# motherboard.net
KiCad netlist of a schematic drawn in Altium Designer
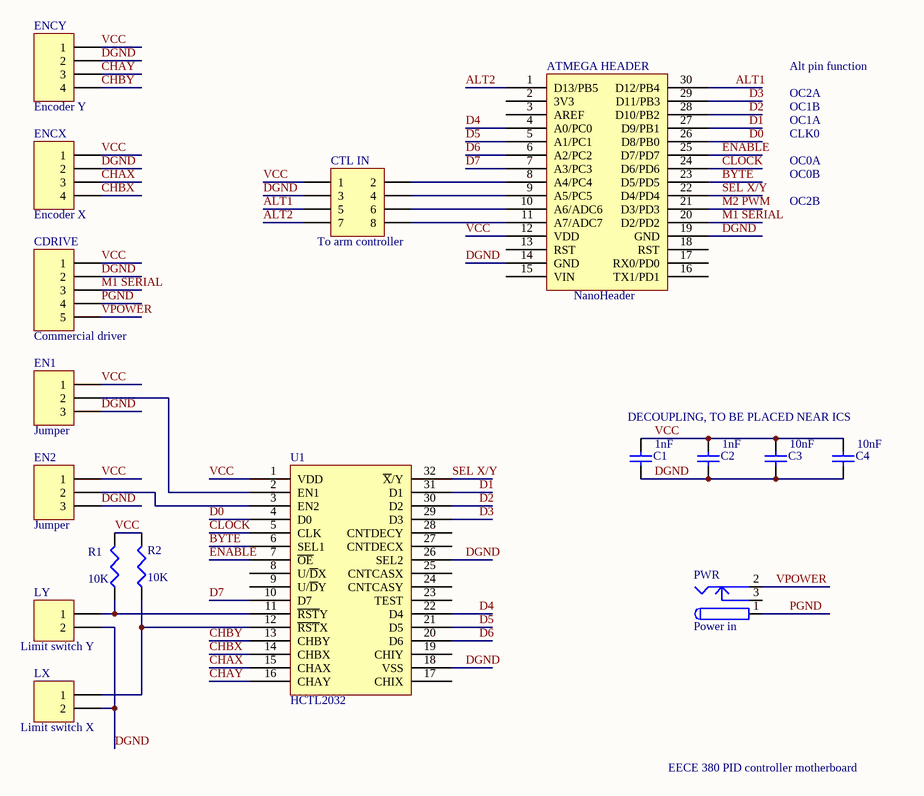
[diagram p0: motherboard.SchDoc]

(export (version "E")
  (design (tool "Eeschema 10.0.6"))
  (components
    (comp (ref "ATMEGA HEADER")
      (value "NanoHeader")
      (footprint "DIP30WIDE")
      (libsource (lib "controllerSchLib") (part "NanoHeader"))
    )
    (comp (ref "C1")
      (value "1nF")
      (footprint "RAD-0.3")
      (description "Capacitor")
      (fields (field (name "PUBLISHER") "Altium Limited"))
      (libsource (lib "Miscellaneous Devices") (part "Cap"))
    )
    (comp (ref "C2")
      (value "1nF")
      (footprint "RAD-0.3")
      (description "Capacitor")
      (fields (field (name "PUBLISHER") "Altium Limited"))
      (libsource (lib "Miscellaneous Devices") (part "Cap"))
    )
    (comp (ref "C3")
      (value "10nF")
      (footprint "RAD-0.3")
      (description "Capacitor")
      (fields (field (name "PUBLISHER") "Altium Limited"))
      (libsource (lib "Miscellaneous Devices") (part "Cap"))
    )
    (comp (ref "C4")
      (value "10nF")
      (footprint "RAD-0.3")
      (description "Capacitor")
      (fields (field (name "PUBLISHER") "Altium Limited"))
      (libsource (lib "Miscellaneous Devices") (part "Cap"))
    )
    (comp (ref "CDRIVE")
      (value "Commercial driver")
      (footprint "HDR1X5_LGE1.0")
      (description "Header, 6-Pin")
      (fields (field (name "PUBLISHER") "Altium Limited"))
      (libsource (lib "PartsDatabaseV13p1") (part "C-Hdr1x5"))
    )
    (comp (ref "CTL IN")
      (value "To arm controller")
      (footprint "HDR2X4_LGE1.0")
      (description "Header, 4-Pin, Dual row")
      (fields (field (name "PUBLISHER") "Altium Limited"))
      (libsource (lib "PartsDatabaseV13p1") (part "C-Hdr2x4"))
    )
    (comp (ref "EN1")
      (value "Jumper")
      (footprint "HDR1X3_LGE1.0")
      (description "Header, 4-Pin")
      (fields (field (name "PUBLISHER") "Altium Limited"))
      (libsource (lib "PartsDatabaseV13p1") (part "C-Hdr1x3"))
    )
    (comp (ref "EN2")
      (value "Jumper")
      (footprint "HDR1X3_LGE1.0")
      (description "Header, 4-Pin")
      (fields (field (name "PUBLISHER") "Altium Limited"))
      (libsource (lib "PartsDatabaseV13p1") (part "C-Hdr1x3"))
    )
    (comp (ref "ENCX")
      (value "Encoder X")
      (footprint "HDR1X4_LGE1.0")
      (description "Header, 4-Pin")
      (fields (field (name "PUBLISHER") "Altium Limited"))
      (libsource (lib "PartsDatabaseV12") (part "C-Hdr1x4"))
    )
    (comp (ref "ENCY")
      (value "Encoder Y")
      (footprint "HDR1X4_LGE1.0")
      (description "Header, 4-Pin")
      (fields (field (name "PUBLISHER") "Altium Limited"))
      (libsource (lib "PartsDatabaseV12") (part "C-Hdr1x4"))
    )
    (comp (ref "LX")
      (value "Limit switch X")
      (footprint "HDR1X2_LGE1.0")
      (description "Header, 2-Pin")
      (fields (field (name "PUBLISHER") "Altium Limited"))
      (libsource (lib "PartsDatabaseV13p1") (part "C-Hdr1x2"))
    )
    (comp (ref "LY")
      (value "Limit switch Y")
      (footprint "HDR1X2_LGE1.0")
      (description "Header, 2-Pin")
      (fields (field (name "PUBLISHER") "Altium Limited"))
      (libsource (lib "PartsDatabaseV13p1") (part "C-Hdr1x2"))
    )
    (comp (ref "PWR")
      (value "Power in")
      (footprint "KLD_XLGE1.2")
      (description "Low Voltage Power Supply Connector")
      (fields (field (name "PUBLISHER") "Altium Limited"))
      (libsource (lib "PartsDatabaseV13p1") (part "C-Pwr"))
    )
    (comp (ref "R1")
      (value "10K")
      (footprint "Res10mm_LGE1.0")
      (description "resistor (specify value)")
      (fields (field (name "PUBLISHER") "Altium Limited"))
      (libsource (lib "PartsDatabaseV13p1") (part "G-Res"))
    )
    (comp (ref "R2")
      (value "10K")
      (footprint "Res10mm_LGE1.0")
      (description "resistor (specify value)")
      (fields (field (name "PUBLISHER") "Altium Limited"))
      (libsource (lib "PartsDatabaseV13p1") (part "G-Res"))
    )
    (comp (ref "U1")
      (value "HCTL2032")
      (footprint "SOIC50P295X100-32L16N")
      (libsource (lib "controllerSchLib") (part "HCTL2032"))
    )
  )
  (nets
    (net (code "1") (name "/ALT1") (class "Default")
      (node (ref "ATMEGA HEADER") (pin "30") (pinfunction "D12/PB4_30") (pintype "passive"))
      (node (ref "CTL IN") (pin "5") (pinfunction "5_5") (pintype "passive"))
    )
    (net (code "2") (name "/ALT2") (class "Default")
      (node (ref "ATMEGA HEADER") (pin "1") (pinfunction "D13/PB5_1") (pintype "passive"))
      (node (ref "CTL IN") (pin "7") (pinfunction "7_7") (pintype "passive"))
    )
    (net (code "3") (name "/BYTE") (class "Default")
      (node (ref "ATMEGA HEADER") (pin "23") (pinfunction "D5/PD5_23") (pintype "passive"))
      (node (ref "U1") (pin "6") (pinfunction "SEL1_6") (pintype "passive"))
    )
    (net (code "4") (name "/CHAX") (class "Default")
      (node (ref "ENCX") (pin "3") (pinfunction "3_3") (pintype "passive"))
      (node (ref "U1") (pin "15") (pinfunction "CHAX_15") (pintype "passive"))
    )
    (net (code "5") (name "/CHAY") (class "Default")
      (node (ref "ENCY") (pin "3") (pinfunction "3_3") (pintype "passive"))
      (node (ref "U1") (pin "16") (pinfunction "CHAY_16") (pintype "passive"))
    )
    (net (code "6") (name "/CHBX") (class "Default")
      (node (ref "ENCX") (pin "4") (pinfunction "4_4") (pintype "passive"))
      (node (ref "U1") (pin "14") (pinfunction "CHBX_14") (pintype "passive"))
    )
    (net (code "7") (name "/CHBY") (class "Default")
      (node (ref "ENCY") (pin "4") (pinfunction "4_4") (pintype "passive"))
      (node (ref "U1") (pin "13") (pinfunction "CHBY_13") (pintype "passive"))
    )
    (net (code "8") (name "/CLOCK") (class "Default")
      (node (ref "ATMEGA HEADER") (pin "24") (pinfunction "D6/PD6_24") (pintype "passive"))
      (node (ref "U1") (pin "5") (pinfunction "CLK_5") (pintype "passive"))
    )
    (net (code "9") (name "/D0") (class "Default")
      (node (ref "ATMEGA HEADER") (pin "26") (pinfunction "D8/PB0_26") (pintype "passive"))
      (node (ref "U1") (pin "4") (pinfunction "D0_4") (pintype "passive"))
    )
    (net (code "10") (name "/D1") (class "Default")
      (node (ref "ATMEGA HEADER") (pin "27") (pinfunction "D9/PB1_27") (pintype "passive"))
      (node (ref "U1") (pin "31") (pinfunction "D1_31") (pintype "passive"))
    )
    (net (code "11") (name "/D2") (class "Default")
      (node (ref "ATMEGA HEADER") (pin "28") (pinfunction "D10/PB2_28") (pintype "passive"))
      (node (ref "U1") (pin "30") (pinfunction "D2_30") (pintype "passive"))
    )
    (net (code "12") (name "/D3") (class "Default")
      (node (ref "ATMEGA HEADER") (pin "29") (pinfunction "D11/PB3_29") (pintype "passive"))
      (node (ref "U1") (pin "29") (pinfunction "D3_29") (pintype "passive"))
    )
    (net (code "13") (name "/D4") (class "Default")
      (node (ref "ATMEGA HEADER") (pin "4") (pinfunction "A0/PC0_4") (pintype "passive"))
      (node (ref "U1") (pin "22") (pinfunction "D4_22") (pintype "passive"))
    )
    (net (code "14") (name "/D5") (class "Default")
      (node (ref "ATMEGA HEADER") (pin "5") (pinfunction "A1/PC1_5") (pintype "passive"))
      (node (ref "U1") (pin "21") (pinfunction "D5_21") (pintype "passive"))
    )
    (net (code "15") (name "/D6") (class "Default")
      (node (ref "ATMEGA HEADER") (pin "6") (pinfunction "A2/PC2_6") (pintype "passive"))
      (node (ref "U1") (pin "20") (pinfunction "D6_20") (pintype "passive"))
    )
    (net (code "16") (name "/D7") (class "Default")
      (node (ref "ATMEGA HEADER") (pin "7") (pinfunction "A3/PC3_7") (pintype "passive"))
      (node (ref "U1") (pin "10") (pinfunction "D7_10") (pintype "passive"))
    )
    (net (code "17") (name "/DGND") (class "Default")
      (node (ref "ATMEGA HEADER") (pin "14") (pinfunction "GND_14") (pintype "passive"))
      (node (ref "ATMEGA HEADER") (pin "19") (pinfunction "GND_19") (pintype "passive"))
      (node (ref "C1") (pin "1") (pinfunction "1_1") (pintype "passive"))
      (node (ref "C2") (pin "1") (pinfunction "1_1") (pintype "passive"))
      (node (ref "C3") (pin "1") (pinfunction "1_1") (pintype "passive"))
      (node (ref "C4") (pin "1") (pinfunction "1_1") (pintype "passive"))
      (node (ref "CDRIVE") (pin "2") (pinfunction "2_2") (pintype "passive"))
      (node (ref "CTL IN") (pin "3") (pinfunction "3_3") (pintype "passive"))
      (node (ref "EN1") (pin "3") (pinfunction "3_3") (pintype "passive"))
      (node (ref "EN2") (pin "3") (pinfunction "3_3") (pintype "passive"))
      (node (ref "ENCX") (pin "2") (pinfunction "2_2") (pintype "passive"))
      (node (ref "ENCY") (pin "2") (pinfunction "2_2") (pintype "passive"))
      (node (ref "LX") (pin "2") (pinfunction "2_2") (pintype "passive"))
      (node (ref "LY") (pin "2") (pinfunction "2_2") (pintype "passive"))
      (node (ref "U1") (pin "18") (pinfunction "VSS_18") (pintype "passive"))
      (node (ref "U1") (pin "26") (pinfunction "SEL2_26") (pintype "passive"))
    )
    (net (code "18") (name "/ENABLE") (class "Default")
      (node (ref "ATMEGA HEADER") (pin "25") (pinfunction "D7/PD7_25") (pintype "passive"))
      (node (ref "U1") (pin "7") (pinfunction "~{OE}_7") (pintype "passive"))
    )
    (net (code "19") (name "/M1 SERIAL") (class "Default")
      (node (ref "ATMEGA HEADER") (pin "20") (pinfunction "D2/PD2_20") (pintype "passive"))
      (node (ref "CDRIVE") (pin "3") (pinfunction "3_3") (pintype "passive"))
    )
    (net (code "20") (name "/M2 PWM") (class "Default")
      (node (ref "ATMEGA HEADER") (pin "21") (pinfunction "D3/PD3_21") (pintype "passive"))
    )
    (net (code "21") (name "/PGND") (class "Default")
      (node (ref "CDRIVE") (pin "4") (pinfunction "4_4") (pintype "passive"))
      (node (ref "PWR") (pin "1") (pinfunction "1_1") (pintype "power_in"))
    )
    (net (code "22") (name "/SEL X{slash}Y") (class "Default")
      (node (ref "ATMEGA HEADER") (pin "22") (pinfunction "D4/PD4_22") (pintype "passive"))
      (node (ref "U1") (pin "32") (pinfunction "~{X}/Y_32") (pintype "passive"))
    )
    (net (code "23") (name "/VCC") (class "Default")
      (node (ref "ATMEGA HEADER") (pin "12") (pinfunction "VDD_12") (pintype "passive"))
      (node (ref "C1") (pin "2") (pinfunction "2_2") (pintype "passive"))
      (node (ref "C2") (pin "2") (pinfunction "2_2") (pintype "passive"))
      (node (ref "C3") (pin "2") (pinfunction "2_2") (pintype "passive"))
      (node (ref "C4") (pin "2") (pinfunction "2_2") (pintype "passive"))
      (node (ref "CDRIVE") (pin "1") (pinfunction "1_1") (pintype "passive"))
      (node (ref "CTL IN") (pin "1") (pinfunction "1_1") (pintype "passive"))
      (node (ref "EN1") (pin "1") (pinfunction "1_1") (pintype "passive"))
      (node (ref "EN2") (pin "1") (pinfunction "1_1") (pintype "passive"))
      (node (ref "ENCX") (pin "1") (pinfunction "1_1") (pintype "passive"))
      (node (ref "ENCY") (pin "1") (pinfunction "1_1") (pintype "passive"))
      (node (ref "R1") (pin "2") (pinfunction "2_2") (pintype "passive"))
      (node (ref "R2") (pin "2") (pinfunction "2_2") (pintype "passive"))
      (node (ref "U1") (pin "1") (pinfunction "VDD_1") (pintype "passive"))
    )
    (net (code "24") (name "/VPOWER") (class "Default")
      (node (ref "CDRIVE") (pin "5") (pinfunction "5_5") (pintype "passive"))
      (node (ref "PWR") (pin "2") (pinfunction "2_2") (pintype "power_in"))
    )
    (net (code "25") (name "Net-(ATMEGA HEADER-A4{slash}PC4)") (class "Default")
      (node (ref "ATMEGA HEADER") (pin "8") (pinfunction "A4/PC4_8") (pintype "passive"))
      (node (ref "CTL IN") (pin "2") (pinfunction "2_2") (pintype "passive"))
    )
    (net (code "26") (name "Net-(ATMEGA HEADER-A5{slash}PC5)") (class "Default")
      (node (ref "ATMEGA HEADER") (pin "9") (pinfunction "A5/PC5_9") (pintype "passive"))
      (node (ref "CTL IN") (pin "4") (pinfunction "4_4") (pintype "passive"))
    )
    (net (code "27") (name "Net-(ATMEGA HEADER-A6{slash}ADC6)") (class "Default")
      (node (ref "ATMEGA HEADER") (pin "10") (pinfunction "A6/ADC6_10") (pintype "passive"))
      (node (ref "CTL IN") (pin "6") (pinfunction "6_6") (pintype "passive"))
    )
    (net (code "28") (name "Net-(ATMEGA HEADER-A7{slash}ADC7)") (class "Default")
      (node (ref "ATMEGA HEADER") (pin "11") (pinfunction "A7/ADC7_11") (pintype "passive"))
      (node (ref "CTL IN") (pin "8") (pinfunction "8_8") (pintype "passive"))
    )
    (net (code "29") (name "Net-(U1-EN1)") (class "Default")
      (node (ref "EN1") (pin "2") (pinfunction "2_2") (pintype "passive"))
      (node (ref "U1") (pin "2") (pinfunction "EN1_2") (pintype "passive"))
    )
    (net (code "30") (name "Net-(U1-EN2)") (class "Default")
      (node (ref "EN2") (pin "2") (pinfunction "2_2") (pintype "passive"))
      (node (ref "U1") (pin "3") (pinfunction "EN2_3") (pintype "passive"))
    )
    (net (code "31") (name "Net-(U1-~{RST}X)") (class "Default")
      (node (ref "LX") (pin "1") (pinfunction "1_1") (pintype "passive"))
      (node (ref "R2") (pin "1") (pinfunction "1_1") (pintype "passive"))
      (node (ref "U1") (pin "12") (pinfunction "~{RST}X_12") (pintype "passive"))
    )
    (net (code "32") (name "Net-(U1-~{RST}Y)") (class "Default")
      (node (ref "LY") (pin "1") (pinfunction "1_1") (pintype "passive"))
      (node (ref "R1") (pin "1") (pinfunction "1_1") (pintype "passive"))
      (node (ref "U1") (pin "11") (pinfunction "~{RST}Y_11") (pintype "passive"))
    )
    (net (code "33") (name "unconnected-(ATMEGA HEADER-3V3-Pad2)") (class "Default")
      (node (ref "ATMEGA HEADER") (pin "2") (pinfunction "3V3_2") (pintype "passive"))
    )
    (net (code "34") (name "unconnected-(ATMEGA HEADER-AREF-Pad3)") (class "Default")
      (node (ref "ATMEGA HEADER") (pin "3") (pinfunction "AREF_3") (pintype "passive"))
    )
    (net (code "35") (name "unconnected-(ATMEGA HEADER-RST-Pad13)") (class "Default")
      (node (ref "ATMEGA HEADER") (pin "13") (pinfunction "RST_13") (pintype "passive"))
    )
    (net (code "36") (name "unconnected-(ATMEGA HEADER-RST-Pad18)") (class "Default")
      (node (ref "ATMEGA HEADER") (pin "18") (pinfunction "RST_18") (pintype "passive"))
    )
    (net (code "37") (name "unconnected-(ATMEGA HEADER-RX0{slash}PD0-Pad17)") (class "Default")
      (node (ref "ATMEGA HEADER") (pin "17") (pinfunction "RX0/PD0_17") (pintype "passive"))
    )
    (net (code "38") (name "unconnected-(ATMEGA HEADER-TX1{slash}PD1-Pad16)") (class "Default")
      (node (ref "ATMEGA HEADER") (pin "16") (pinfunction "TX1/PD1_16") (pintype "passive"))
    )
    (net (code "39") (name "unconnected-(ATMEGA HEADER-VIN-Pad15)") (class "Default")
      (node (ref "ATMEGA HEADER") (pin "15") (pinfunction "VIN_15") (pintype "passive"))
    )
    (net (code "40") (name "unconnected-(PWR-Pad3)") (class "Default")
      (node (ref "PWR") (pin "3") (pinfunction "3_3") (pintype "power_in"))
    )
    (net (code "41") (name "unconnected-(U1-CHIX-Pad17)") (class "Default")
      (node (ref "U1") (pin "17") (pinfunction "CHIX_17") (pintype "passive"))
    )
    (net (code "42") (name "unconnected-(U1-CHIY-Pad19)") (class "Default")
      (node (ref "U1") (pin "19") (pinfunction "CHIY_19") (pintype "passive"))
    )
    (net (code "43") (name "unconnected-(U1-CNTCASX-Pad25)") (class "Default")
      (node (ref "U1") (pin "25") (pinfunction "CNTCASX_25") (pintype "passive"))
    )
    (net (code "44") (name "unconnected-(U1-CNTCASY-Pad24)") (class "Default")
      (node (ref "U1") (pin "24") (pinfunction "CNTCASY_24") (pintype "passive"))
    )
    (net (code "45") (name "unconnected-(U1-CNTDECX-Pad27)") (class "Default")
      (node (ref "U1") (pin "27") (pinfunction "CNTDECX_27") (pintype "passive"))
    )
    (net (code "46") (name "unconnected-(U1-CNTDECY-Pad28)") (class "Default")
      (node (ref "U1") (pin "28") (pinfunction "CNTDECY_28") (pintype "passive"))
    )
    (net (code "47") (name "unconnected-(U1-TEST-Pad23)") (class "Default")
      (node (ref "U1") (pin "23") (pinfunction "TEST_23") (pintype "passive"))
    )
    (net (code "48") (name "unconnected-(U1-U{slash}~{D}X-Pad8)") (class "Default")
      (node (ref "U1") (pin "8") (pinfunction "U/~{D}X_8") (pintype "passive"))
    )
    (net (code "49") (name "unconnected-(U1-U{slash}~{D}Y-Pad9)") (class "Default")
      (node (ref "U1") (pin "9") (pinfunction "U/~{D}Y_9") (pintype "passive"))
    )
  )
)
